# rapidshark-h-bridge-mk-1_0.net
KiCad netlist of a schematic drawn in EAGLE
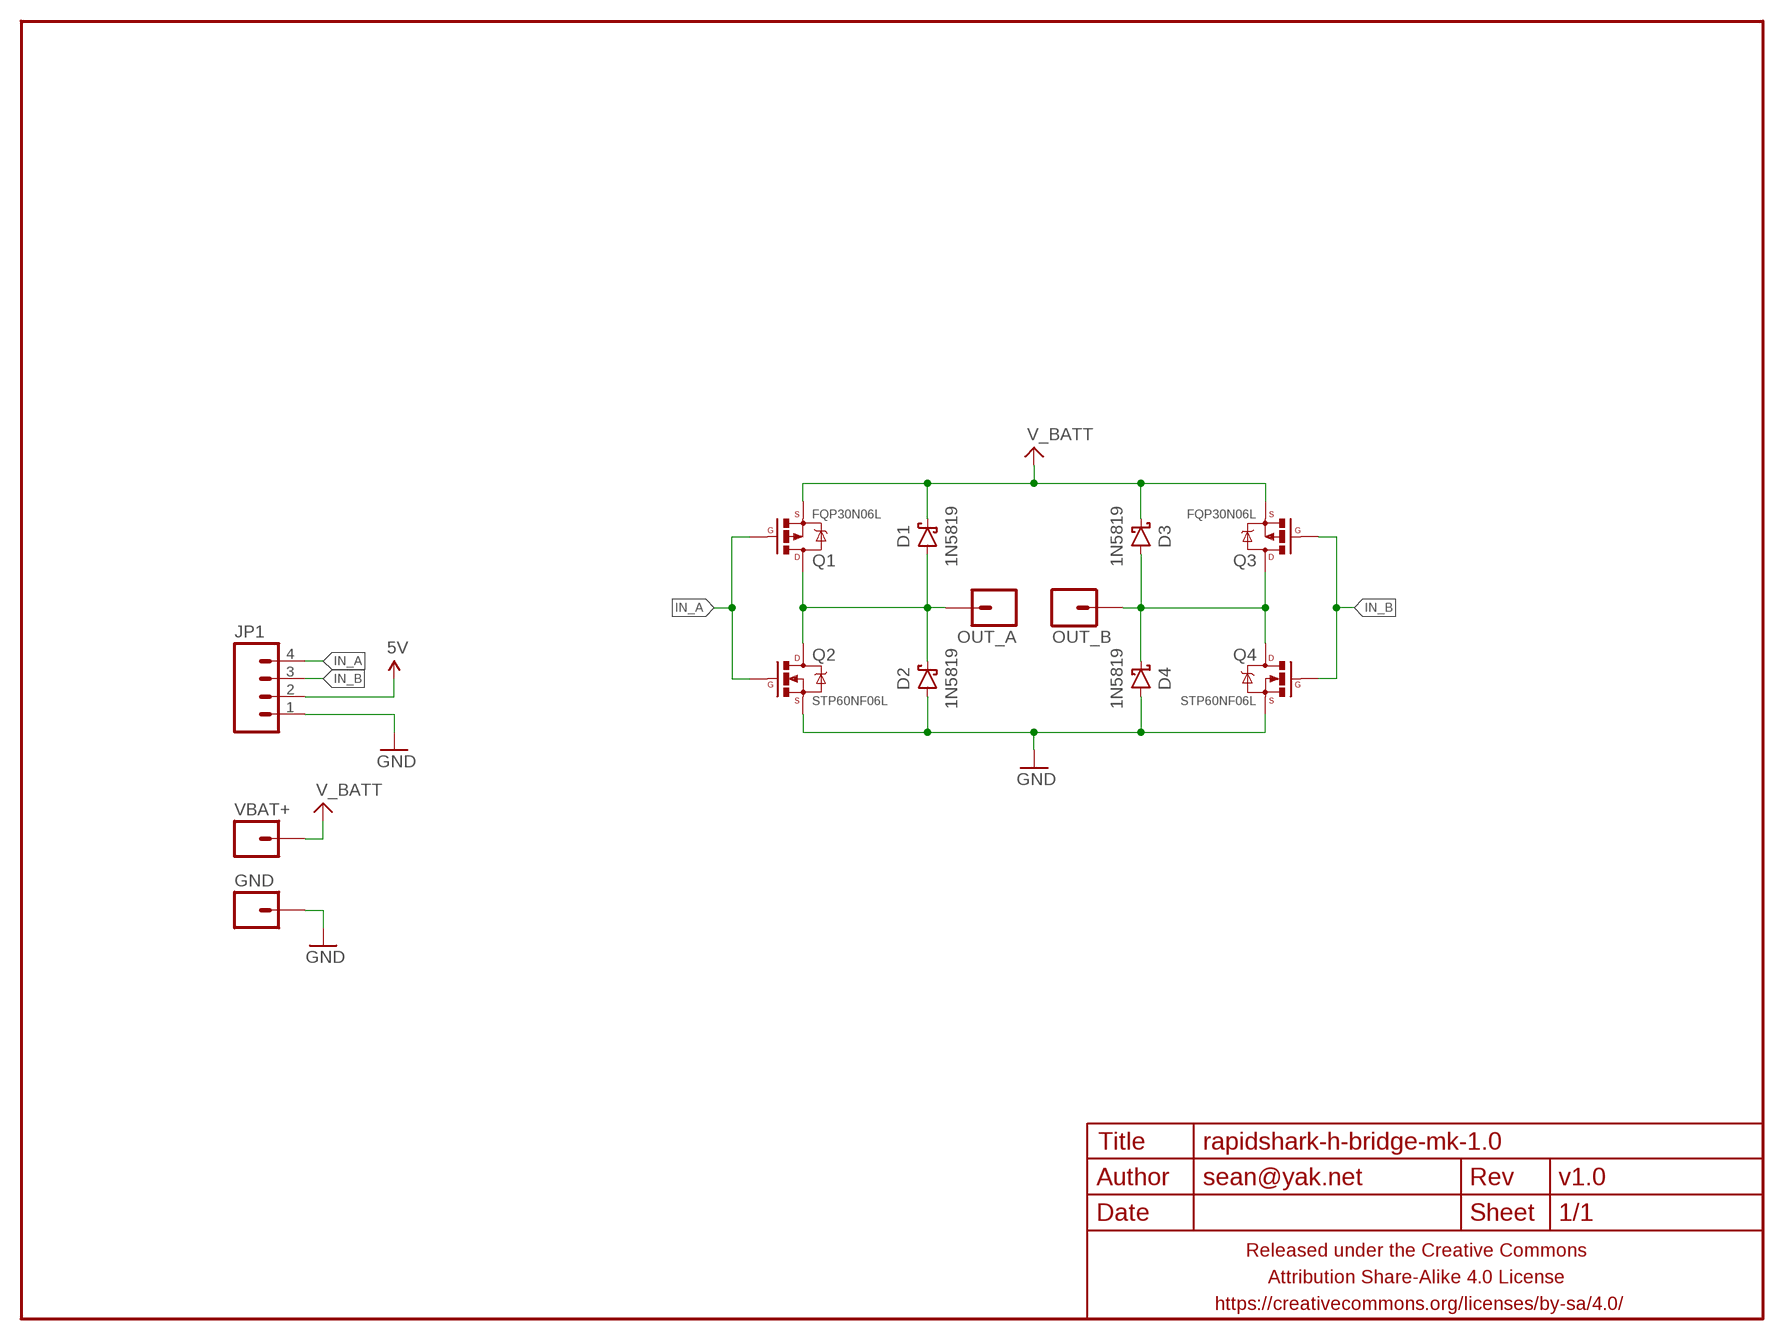
[diagram p0: schematic, sheet 1]

(export (version "E")
  (design (tool "Eeschema 10.0.6"))
  (components
    (comp (ref "D1")
      (value "1N5819")
      (footprint "eagle-import:DIODE-SCHOTTKY-10.16MM")
      (libsource (lib "eagle-import") (part "DIODE-SCHOTTKYPTH-10.16MM"))
    )
    (comp (ref "D2")
      (value "1N5819")
      (footprint "eagle-import:DIODE-SCHOTTKY-10.16MM")
      (libsource (lib "eagle-import") (part "DIODE-SCHOTTKYPTH-10.16MM"))
    )
    (comp (ref "D3")
      (value "1N5819")
      (footprint "eagle-import:DIODE-SCHOTTKY-10.16MM")
      (libsource (lib "eagle-import") (part "DIODE-SCHOTTKYPTH-10.16MM"))
    )
    (comp (ref "D4")
      (value "1N5819")
      (footprint "eagle-import:DIODE-SCHOTTKY-10.16MM")
      (libsource (lib "eagle-import") (part "DIODE-SCHOTTKYPTH-10.16MM"))
    )
    (comp (ref "FRAME1")
      (value "FRAME-LETTERNO_PACKAGE")
      (footprint "eagle-import:DUMMY")
      (fields (field (name "DESIGNER") "sean@yak.net") (field (name "VERSION") "v1.0"))
      (libsource (lib "eagle-import") (part "FRAME-LETTERNO_PACKAGE"))
    )
    (comp (ref "GND")
      (value "M0112AWG")
      (footprint "eagle-import:1X01-12AWG")
      (libsource (lib "eagle-import") (part "M0112AWG"))
    )
    (comp (ref "JP1")
      (value "M04PTH")
      (footprint "eagle-import:1X04-PTH-VERT")
      (libsource (lib "eagle-import") (part "M04PTH"))
    )
    (comp (ref "OUT_A")
      (value "M0112AWG")
      (footprint "eagle-import:1X01-12AWG")
      (libsource (lib "eagle-import") (part "M0112AWG"))
    )
    (comp (ref "OUT_B")
      (value "M0112AWG")
      (footprint "eagle-import:1X01-12AWG")
      (libsource (lib "eagle-import") (part "M0112AWG"))
    )
    (comp (ref "Q1")
      (value "FQP30N06L")
      (footprint "eagle-import:TO220-THERMPAD")
      (libsource (lib "eagle-import") (part "MOSFET-PCHANNELFQP30P06L"))
    )
    (comp (ref "Q2")
      (value "STP60NF06L")
      (footprint "eagle-import:TO220-THERMPAD")
      (libsource (lib "eagle-import") (part "MOSFET-NCHANNELTO-220"))
    )
    (comp (ref "Q3")
      (value "FQP30N06L")
      (footprint "eagle-import:TO220-THERMPAD")
      (libsource (lib "eagle-import") (part "MOSFET-PCHANNELFQP30P06L"))
    )
    (comp (ref "Q4")
      (value "STP60NF06L")
      (footprint "eagle-import:TO220-THERMPAD")
      (libsource (lib "eagle-import") (part "MOSFET-NCHANNELTO-220"))
    )
    (comp (ref "VBAT+")
      (value "M0112AWG")
      (footprint "eagle-import:1X01-12AWG")
      (libsource (lib "eagle-import") (part "M0112AWG"))
    )
  )
  (nets
    (net (code "1") (name "5V") (class "Default")
      (node (ref "JP1") (pin "2") (pinfunction "2_2") (pintype "passive"))
    )
    (net (code "2") (name "GND") (class "Default")
      (node (ref "D2") (pin "A") (pinfunction "A_A") (pintype "passive"))
      (node (ref "D4") (pin "A") (pinfunction "A_A") (pintype "passive"))
      (node (ref "GND") (pin "1") (pinfunction "1_1") (pintype "passive"))
      (node (ref "JP1") (pin "1") (pinfunction "1_1") (pintype "passive"))
      (node (ref "Q2") (pin "3") (pinfunction "S_3") (pintype "passive"))
      (node (ref "Q4") (pin "3") (pinfunction "S_3") (pintype "passive"))
    )
    (net (code "3") (name "IN_A") (class "Default")
      (node (ref "JP1") (pin "4") (pinfunction "4_4") (pintype "passive"))
      (node (ref "Q1") (pin "1") (pinfunction "G_1") (pintype "passive"))
      (node (ref "Q2") (pin "1") (pinfunction "G_1") (pintype "passive"))
    )
    (net (code "4") (name "IN_B") (class "Default")
      (node (ref "JP1") (pin "3") (pinfunction "3_3") (pintype "passive"))
      (node (ref "Q3") (pin "1") (pinfunction "G_1") (pintype "passive"))
      (node (ref "Q4") (pin "1") (pinfunction "G_1") (pintype "passive"))
    )
    (net (code "5") (name "Net-(D1-PadA)") (class "Default")
      (node (ref "D1") (pin "A") (pinfunction "A_A") (pintype "passive"))
      (node (ref "D2") (pin "C") (pinfunction "C_C") (pintype "passive"))
      (node (ref "OUT_A") (pin "1") (pinfunction "1_1") (pintype "passive"))
      (node (ref "Q1") (pin "2@1") (pinfunction "D_2@1") (pintype "passive"))
      (node (ref "Q1") (pin "2@2") (pinfunction "D_2@2") (pintype "passive"))
      (node (ref "Q2") (pin "2@1") (pinfunction "D_2@1") (pintype "passive"))
      (node (ref "Q2") (pin "2@2") (pinfunction "D_2@2") (pintype "passive"))
    )
    (net (code "6") (name "Net-(D3-PadA)") (class "Default")
      (node (ref "D3") (pin "A") (pinfunction "A_A") (pintype "passive"))
      (node (ref "D4") (pin "C") (pinfunction "C_C") (pintype "passive"))
      (node (ref "OUT_B") (pin "1") (pinfunction "1_1") (pintype "passive"))
      (node (ref "Q3") (pin "2@1") (pinfunction "D_2@1") (pintype "passive"))
      (node (ref "Q3") (pin "2@2") (pinfunction "D_2@2") (pintype "passive"))
      (node (ref "Q4") (pin "2@1") (pinfunction "D_2@1") (pintype "passive"))
      (node (ref "Q4") (pin "2@2") (pinfunction "D_2@2") (pintype "passive"))
    )
    (net (code "7") (name "V_BATT") (class "Default")
      (node (ref "D1") (pin "C") (pinfunction "C_C") (pintype "passive"))
      (node (ref "D3") (pin "C") (pinfunction "C_C") (pintype "passive"))
      (node (ref "Q1") (pin "3") (pinfunction "S_3") (pintype "passive"))
      (node (ref "Q3") (pin "3") (pinfunction "S_3") (pintype "passive"))
      (node (ref "VBAT+") (pin "1") (pinfunction "1_1") (pintype "passive"))
    )
  )
)
